# lcdpanel.net
KiCad netlist of a schematic drawn in EAGLE
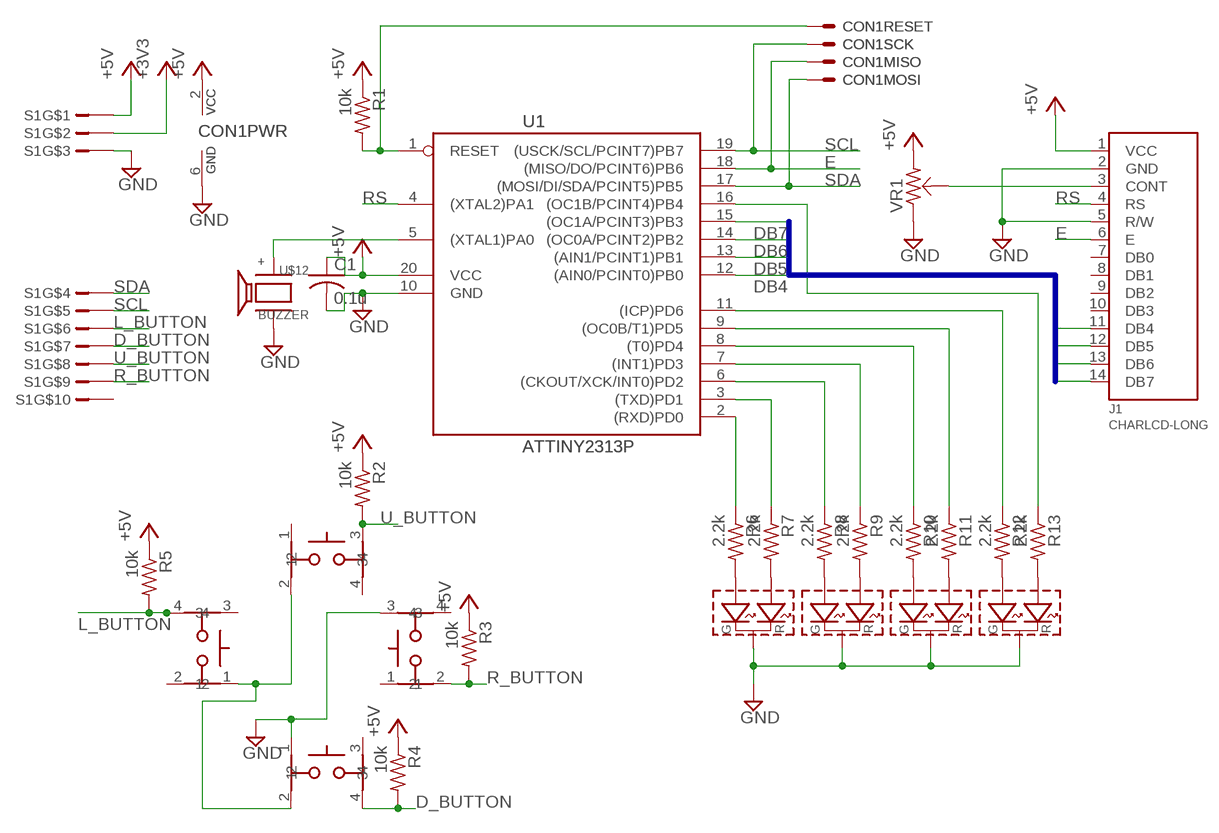
[diagram p0: schematic, sheet 1]

(export (version "E")
  (design (tool "Eeschema 10.0.6"))
  (components
    (comp (ref "C1")
      (value "0.1u")
      (footprint "eagle-import:2012-C")
      (libsource (lib "eagle-import") (part "C-2012"))
    )
    (comp (ref "CON1")
      (value "AVRISP-NEWSYMBOL-ML6")
      (footprint "eagle-import:ML6")
      (libsource (lib "eagle-import") (part "AVRISP-NEWSYMBOL-ML6"))
    )
    (comp (ref "D1")
      (value "LED-RG-3MM")
      (footprint "eagle-import:LED-2COL-3MM")
      (libsource (lib "eagle-import") (part "LED-RG-3MM"))
    )
    (comp (ref "D2")
      (value "LED-RG-3MM")
      (footprint "eagle-import:LED-2COL-3MM")
      (libsource (lib "eagle-import") (part "LED-RG-3MM"))
    )
    (comp (ref "D3")
      (value "LED-RG-3MM")
      (footprint "eagle-import:LED-2COL-3MM")
      (libsource (lib "eagle-import") (part "LED-RG-3MM"))
    )
    (comp (ref "D4")
      (value "LED-RG-3MM")
      (footprint "eagle-import:LED-2COL-3MM")
      (libsource (lib "eagle-import") (part "LED-RG-3MM"))
    )
    (comp (ref "J1")
      (value "CHARLCD-LONG")
      (footprint "eagle-import:CHARLCD-7X2-LONG")
      (libsource (lib "eagle-import") (part "CHARLCD-LONG"))
    )
    (comp (ref "R1")
      (value "10k")
      (footprint "eagle-import:1608")
      (libsource (lib "eagle-import") (part "R-1608"))
    )
    (comp (ref "R2")
      (value "10k")
      (footprint "eagle-import:1608")
      (libsource (lib "eagle-import") (part "R-1608"))
    )
    (comp (ref "R3")
      (value "10k")
      (footprint "eagle-import:1608")
      (libsource (lib "eagle-import") (part "R-1608"))
    )
    (comp (ref "R4")
      (value "10k")
      (footprint "eagle-import:1608")
      (libsource (lib "eagle-import") (part "R-1608"))
    )
    (comp (ref "R5")
      (value "10k")
      (footprint "eagle-import:1608")
      (libsource (lib "eagle-import") (part "R-1608"))
    )
    (comp (ref "R6")
      (value "2.2k")
      (footprint "eagle-import:1608")
      (libsource (lib "eagle-import") (part "R-1608"))
    )
    (comp (ref "R7")
      (value "2.2k")
      (footprint "eagle-import:1608")
      (libsource (lib "eagle-import") (part "R-1608"))
    )
    (comp (ref "R8")
      (value "2.2k")
      (footprint "eagle-import:1608")
      (libsource (lib "eagle-import") (part "R-1608"))
    )
    (comp (ref "R9")
      (value "2.2k")
      (footprint "eagle-import:1608")
      (libsource (lib "eagle-import") (part "R-1608"))
    )
    (comp (ref "R10")
      (value "2.2k")
      (footprint "eagle-import:1608")
      (libsource (lib "eagle-import") (part "R-1608"))
    )
    (comp (ref "R11")
      (value "2.2k")
      (footprint "eagle-import:1608")
      (libsource (lib "eagle-import") (part "R-1608"))
    )
    (comp (ref "R12")
      (value "2.2k")
      (footprint "eagle-import:1608")
      (libsource (lib "eagle-import") (part "R-1608"))
    )
    (comp (ref "R13")
      (value "2.2k")
      (footprint "eagle-import:1608")
      (libsource (lib "eagle-import") (part "R-1608"))
    )
    (comp (ref "S1")
      (value "10B-PH")
      (footprint "eagle-import:S10B-PH")
      (libsource (lib "eagle-import") (part "?10B-PH"))
    )
    (comp (ref "SW1")
      (value "PUSHSW")
      (footprint "eagle-import:PUSHSW")
      (libsource (lib "eagle-import") (part "PUSHSW"))
    )
    (comp (ref "SW2")
      (value "PUSHSW")
      (footprint "eagle-import:PUSHSW")
      (libsource (lib "eagle-import") (part "PUSHSW"))
    )
    (comp (ref "SW3")
      (value "PUSHSW")
      (footprint "eagle-import:PUSHSW")
      (libsource (lib "eagle-import") (part "PUSHSW"))
    )
    (comp (ref "SW4")
      (value "PUSHSW")
      (footprint "eagle-import:PUSHSW")
      (libsource (lib "eagle-import") (part "PUSHSW"))
    )
    (comp (ref "U$12")
      (value "BUZZER")
      (footprint "eagle-import:BUZZER")
      (libsource (lib "eagle-import") (part "BUZZER"))
    )
    (comp (ref "U1")
      (value "ATTINY2313P")
      (footprint "eagle-import:DIL20")
      (libsource (lib "eagle-import") (part "ATTINY2313P"))
    )
    (comp (ref "VR1")
      (value "VR")
      (footprint "eagle-import:VR-637A")
      (libsource (lib "eagle-import") (part "VR"))
    )
  )
  (nets
    (net (code "1") (name "+3V3") (class "Default")
      (node (ref "S1") (pin "P$2") (pinfunction "1_P$2") (pintype "passive"))
    )
    (net (code "2") (name "+5V") (class "Default")
      (node (ref "C1") (pin "1") (pinfunction "1_1") (pintype "passive"))
      (node (ref "CON1") (pin "2") (pinfunction "VCC_2") (pintype "power_in"))
      (node (ref "J1") (pin "1") (pinfunction "VCC_1") (pintype "bidirectional"))
      (node (ref "R1") (pin "1") (pinfunction "1_1") (pintype "passive"))
      (node (ref "R2") (pin "1") (pinfunction "1_1") (pintype "passive"))
      (node (ref "R3") (pin "1") (pinfunction "1_1") (pintype "passive"))
      (node (ref "R4") (pin "1") (pinfunction "1_1") (pintype "passive"))
      (node (ref "R5") (pin "1") (pinfunction "1_1") (pintype "passive"))
      (node (ref "S1") (pin "P$1") (pinfunction "1_P$1") (pintype "passive"))
      (node (ref "U1") (pin "20") (pinfunction "VCC_20") (pintype "power_in"))
      (node (ref "VR1") (pin "2") (pinfunction "2_2") (pintype "passive"))
    )
    (net (code "3") (name "/DB4") (class "Default")
      (node (ref "J1") (pin "11") (pinfunction "DB4_11") (pintype "bidirectional"))
      (node (ref "U1") (pin "12") (pinfunction "(AIN0/PCINT0)PB0_12") (pintype "bidirectional"))
    )
    (net (code "4") (name "/DB5") (class "Default")
      (node (ref "J1") (pin "12") (pinfunction "DB5_12") (pintype "bidirectional"))
      (node (ref "U1") (pin "13") (pinfunction "(AIN1/PCINT1)PB1_13") (pintype "bidirectional"))
    )
    (net (code "5") (name "/DB6") (class "Default")
      (node (ref "J1") (pin "13") (pinfunction "DB6_13") (pintype "bidirectional"))
      (node (ref "U1") (pin "14") (pinfunction "(OC0A/PCINT2)PB2_14") (pintype "bidirectional"))
    )
    (net (code "6") (name "/DB7") (class "Default")
      (node (ref "J1") (pin "14") (pinfunction "DB7_14") (pintype "bidirectional"))
      (node (ref "U1") (pin "15") (pinfunction "(OC1A/PCINT3)PB3_15") (pintype "bidirectional"))
    )
    (net (code "7") (name "/D_BUTTON") (class "Default")
      (node (ref "R4") (pin "2") (pinfunction "2_2") (pintype "passive"))
      (node (ref "S1") (pin "P$7") (pinfunction "1_P$7") (pintype "passive"))
      (node (ref "SW4") (pin "4") (pinfunction "4_4") (pintype "bidirectional"))
    )
    (net (code "8") (name "/E") (class "Default")
      (node (ref "CON1") (pin "1") (pinfunction "S_1") (pintype "passive"))
      (node (ref "J1") (pin "6") (pinfunction "E_6") (pintype "bidirectional"))
      (node (ref "U1") (pin "18") (pinfunction "(MISO/DO/PCINT6)PB6_18") (pintype "bidirectional"))
    )
    (net (code "9") (name "/L_BUTTON") (class "Default")
      (node (ref "R5") (pin "2") (pinfunction "2_2") (pintype "passive"))
      (node (ref "S1") (pin "P$6") (pinfunction "1_P$6") (pintype "passive"))
      (node (ref "SW2") (pin "4") (pinfunction "4_4") (pintype "bidirectional"))
    )
    (net (code "10") (name "/RS") (class "Default")
      (node (ref "J1") (pin "4") (pinfunction "RS_4") (pintype "bidirectional"))
      (node (ref "U1") (pin "4") (pinfunction "(XTAL2)PA1_4") (pintype "bidirectional"))
    )
    (net (code "11") (name "/R_BUTTON") (class "Default")
      (node (ref "R3") (pin "2") (pinfunction "2_2") (pintype "passive"))
      (node (ref "S1") (pin "P$9") (pinfunction "1_P$9") (pintype "passive"))
      (node (ref "SW3") (pin "2") (pinfunction "2_2") (pintype "bidirectional"))
    )
    (net (code "12") (name "/SCL") (class "Default")
      (node (ref "CON1") (pin "3") (pinfunction "S_3") (pintype "passive"))
      (node (ref "S1") (pin "P$5") (pinfunction "1_P$5") (pintype "passive"))
      (node (ref "U1") (pin "19") (pinfunction "(USCK/SCL/PCINT7)PB7_19") (pintype "bidirectional"))
    )
    (net (code "13") (name "/SDA") (class "Default")
      (node (ref "CON1") (pin "4") (pinfunction "S_4") (pintype "passive"))
      (node (ref "S1") (pin "P$4") (pinfunction "1_P$4") (pintype "passive"))
      (node (ref "U1") (pin "17") (pinfunction "(MOSI/DI/SDA/PCINT5)PB5_17") (pintype "bidirectional"))
    )
    (net (code "14") (name "/U_BUTTON") (class "Default")
      (node (ref "R2") (pin "2") (pinfunction "2_2") (pintype "passive"))
      (node (ref "S1") (pin "P$8") (pinfunction "1_P$8") (pintype "passive"))
      (node (ref "SW1") (pin "3") (pinfunction "3_3") (pintype "bidirectional"))
    )
    (net (code "15") (name "GND") (class "Default")
      (node (ref "C1") (pin "2") (pinfunction "2_2") (pintype "passive"))
      (node (ref "CON1") (pin "6") (pinfunction "GND_6") (pintype "power_in"))
      (node (ref "D1") (pin "K") (pinfunction "K_K") (pintype "bidirectional"))
      (node (ref "D2") (pin "K") (pinfunction "K_K") (pintype "bidirectional"))
      (node (ref "D3") (pin "K") (pinfunction "K_K") (pintype "bidirectional"))
      (node (ref "D4") (pin "K") (pinfunction "K_K") (pintype "bidirectional"))
      (node (ref "J1") (pin "2") (pinfunction "GND_2") (pintype "bidirectional"))
      (node (ref "J1") (pin "5") (pinfunction "R/W_5") (pintype "bidirectional"))
      (node (ref "S1") (pin "P$3") (pinfunction "1_P$3") (pintype "passive"))
      (node (ref "SW3") (pin "3") (pinfunction "3_3") (pintype "bidirectional"))
      (node (ref "SW4") (pin "1") (pinfunction "1_1") (pintype "bidirectional"))
      (node (ref "U$12") (pin "-") (pinfunction "-_-") (pintype "bidirectional"))
      (node (ref "U1") (pin "10") (pinfunction "GND_10") (pintype "power_in"))
      (node (ref "VR1") (pin "1") (pinfunction "1_1") (pintype "passive"))
    )
    (net (code "16") (name "Net-(CON1D-S)") (class "Default")
      (node (ref "CON1") (pin "5") (pinfunction "S_5") (pintype "passive"))
      (node (ref "R1") (pin "2") (pinfunction "2_2") (pintype "passive"))
      (node (ref "U1") (pin "1") (pinfunction "RESET_1") (pintype "bidirectional"))
    )
    (net (code "17") (name "Net-(D1-G_A)") (class "Default")
      (node (ref "D1") (pin "YG") (pinfunction "G_A_YG") (pintype "bidirectional"))
      (node (ref "R6") (pin "2") (pinfunction "2_2") (pintype "passive"))
    )
    (net (code "18") (name "Net-(D1-R_A)") (class "Default")
      (node (ref "D1") (pin "R") (pinfunction "R_A_R") (pintype "bidirectional"))
      (node (ref "R7") (pin "2") (pinfunction "2_2") (pintype "passive"))
    )
    (net (code "19") (name "Net-(D2-G_A)") (class "Default")
      (node (ref "D2") (pin "YG") (pinfunction "G_A_YG") (pintype "bidirectional"))
      (node (ref "R8") (pin "2") (pinfunction "2_2") (pintype "passive"))
    )
    (net (code "20") (name "Net-(D2-R_A)") (class "Default")
      (node (ref "D2") (pin "R") (pinfunction "R_A_R") (pintype "bidirectional"))
      (node (ref "R9") (pin "2") (pinfunction "2_2") (pintype "passive"))
    )
    (net (code "21") (name "Net-(D3-G_A)") (class "Default")
      (node (ref "D3") (pin "YG") (pinfunction "G_A_YG") (pintype "bidirectional"))
      (node (ref "R10") (pin "2") (pinfunction "2_2") (pintype "passive"))
    )
    (net (code "22") (name "Net-(D3-R_A)") (class "Default")
      (node (ref "D3") (pin "R") (pinfunction "R_A_R") (pintype "bidirectional"))
      (node (ref "R11") (pin "2") (pinfunction "2_2") (pintype "passive"))
    )
    (net (code "23") (name "Net-(D4-G_A)") (class "Default")
      (node (ref "D4") (pin "YG") (pinfunction "G_A_YG") (pintype "bidirectional"))
      (node (ref "R12") (pin "2") (pinfunction "2_2") (pintype "passive"))
    )
    (net (code "24") (name "Net-(D4-R_A)") (class "Default")
      (node (ref "D4") (pin "R") (pinfunction "R_A_R") (pintype "bidirectional"))
      (node (ref "R13") (pin "2") (pinfunction "2_2") (pintype "passive"))
    )
    (net (code "25") (name "Net-(J1-CONT)") (class "Default")
      (node (ref "J1") (pin "3") (pinfunction "CONT_3") (pintype "bidirectional"))
      (node (ref "VR1") (pin "BR") (pinfunction "BR_BR") (pintype "passive"))
    )
    (net (code "26") (name "Net-(SW1-Pad2)") (class "Default")
      (node (ref "SW1") (pin "2") (pinfunction "2_2") (pintype "bidirectional"))
      (node (ref "SW2") (pin "1") (pinfunction "1_1") (pintype "bidirectional"))
      (node (ref "SW4") (pin "2") (pinfunction "2_2") (pintype "bidirectional"))
    )
    (net (code "27") (name "Net-(U1-(CKOUT{slash}XCK{slash}INT0)PD2)") (class "Default")
      (node (ref "R8") (pin "1") (pinfunction "1_1") (pintype "passive"))
      (node (ref "U1") (pin "6") (pinfunction "(CKOUT/XCK/INT0)PD2_6") (pintype "bidirectional"))
    )
    (net (code "28") (name "Net-(U1-(ICP)PD6)") (class "Default")
      (node (ref "R12") (pin "1") (pinfunction "1_1") (pintype "passive"))
      (node (ref "U1") (pin "11") (pinfunction "(ICP)PD6_11") (pintype "bidirectional"))
    )
    (net (code "29") (name "Net-(U1-(INT1)PD3)") (class "Default")
      (node (ref "R9") (pin "1") (pinfunction "1_1") (pintype "passive"))
      (node (ref "U1") (pin "7") (pinfunction "(INT1)PD3_7") (pintype "bidirectional"))
    )
    (net (code "30") (name "Net-(U1-(OC0B{slash}T1)PD5)") (class "Default")
      (node (ref "R11") (pin "1") (pinfunction "1_1") (pintype "passive"))
      (node (ref "U1") (pin "9") (pinfunction "(OC0B/T1)PD5_9") (pintype "bidirectional"))
    )
    (net (code "31") (name "Net-(U1-(OC1B{slash}PCINT4)PB4)") (class "Default")
      (node (ref "R13") (pin "1") (pinfunction "1_1") (pintype "passive"))
      (node (ref "U1") (pin "16") (pinfunction "(OC1B/PCINT4)PB4_16") (pintype "bidirectional"))
    )
    (net (code "32") (name "Net-(U1-(RXD)PD0)") (class "Default")
      (node (ref "R6") (pin "1") (pinfunction "1_1") (pintype "passive"))
      (node (ref "U1") (pin "2") (pinfunction "(RXD)PD0_2") (pintype "bidirectional"))
    )
    (net (code "33") (name "Net-(U1-(T0)PD4)") (class "Default")
      (node (ref "R10") (pin "1") (pinfunction "1_1") (pintype "passive"))
      (node (ref "U1") (pin "8") (pinfunction "(T0)PD4_8") (pintype "bidirectional"))
    )
    (net (code "34") (name "Net-(U1-(TXD)PD1)") (class "Default")
      (node (ref "R7") (pin "1") (pinfunction "1_1") (pintype "passive"))
      (node (ref "U1") (pin "3") (pinfunction "(TXD)PD1_3") (pintype "bidirectional"))
    )
    (net (code "35") (name "Net-(U1-(XTAL1)PA0)") (class "Default")
      (node (ref "U$12") (pin "+") (pinfunction "+_+") (pintype "bidirectional"))
      (node (ref "U1") (pin "5") (pinfunction "(XTAL1)PA0_5") (pintype "bidirectional"))
    )
    (net (code "36") (name "unconnected-(J1-DB0-Pad7)") (class "Default")
      (node (ref "J1") (pin "7") (pinfunction "DB0_7") (pintype "bidirectional"))
    )
    (net (code "37") (name "unconnected-(J1-DB1-Pad8)") (class "Default")
      (node (ref "J1") (pin "8") (pinfunction "DB1_8") (pintype "bidirectional"))
    )
    (net (code "38") (name "unconnected-(J1-DB2-Pad9)") (class "Default")
      (node (ref "J1") (pin "9") (pinfunction "DB2_9") (pintype "bidirectional"))
    )
    (net (code "39") (name "unconnected-(J1-DB3-Pad10)") (class "Default")
      (node (ref "J1") (pin "10") (pinfunction "DB3_10") (pintype "bidirectional"))
    )
    (net (code "40") (name "unconnected-(S1B-1-PadP$10)") (class "Default")
      (node (ref "S1") (pin "P$10") (pinfunction "1_P$10") (pintype "passive"))
    )
    (net (code "41") (name "unconnected-(SW1-Pad1)") (class "Default")
      (node (ref "SW1") (pin "1") (pinfunction "1_1") (pintype "bidirectional"))
    )
    (net (code "42") (name "unconnected-(SW1-Pad4)") (class "Default")
      (node (ref "SW1") (pin "4") (pinfunction "4_4") (pintype "bidirectional"))
    )
    (net (code "43") (name "unconnected-(SW2-Pad2)") (class "Default")
      (node (ref "SW2") (pin "2") (pinfunction "2_2") (pintype "bidirectional"))
    )
    (net (code "44") (name "unconnected-(SW2-Pad3)") (class "Default")
      (node (ref "SW2") (pin "3") (pinfunction "3_3") (pintype "bidirectional"))
    )
    (net (code "45") (name "unconnected-(SW3-Pad1)") (class "Default")
      (node (ref "SW3") (pin "1") (pinfunction "1_1") (pintype "bidirectional"))
    )
    (net (code "46") (name "unconnected-(SW3-Pad4)") (class "Default")
      (node (ref "SW3") (pin "4") (pinfunction "4_4") (pintype "bidirectional"))
    )
    (net (code "47") (name "unconnected-(SW4-Pad3)") (class "Default")
      (node (ref "SW4") (pin "3") (pinfunction "3_3") (pintype "bidirectional"))
    )
  )
)
